# ramtotsop.net
KiCad netlist of a schematic drawn in EAGLE
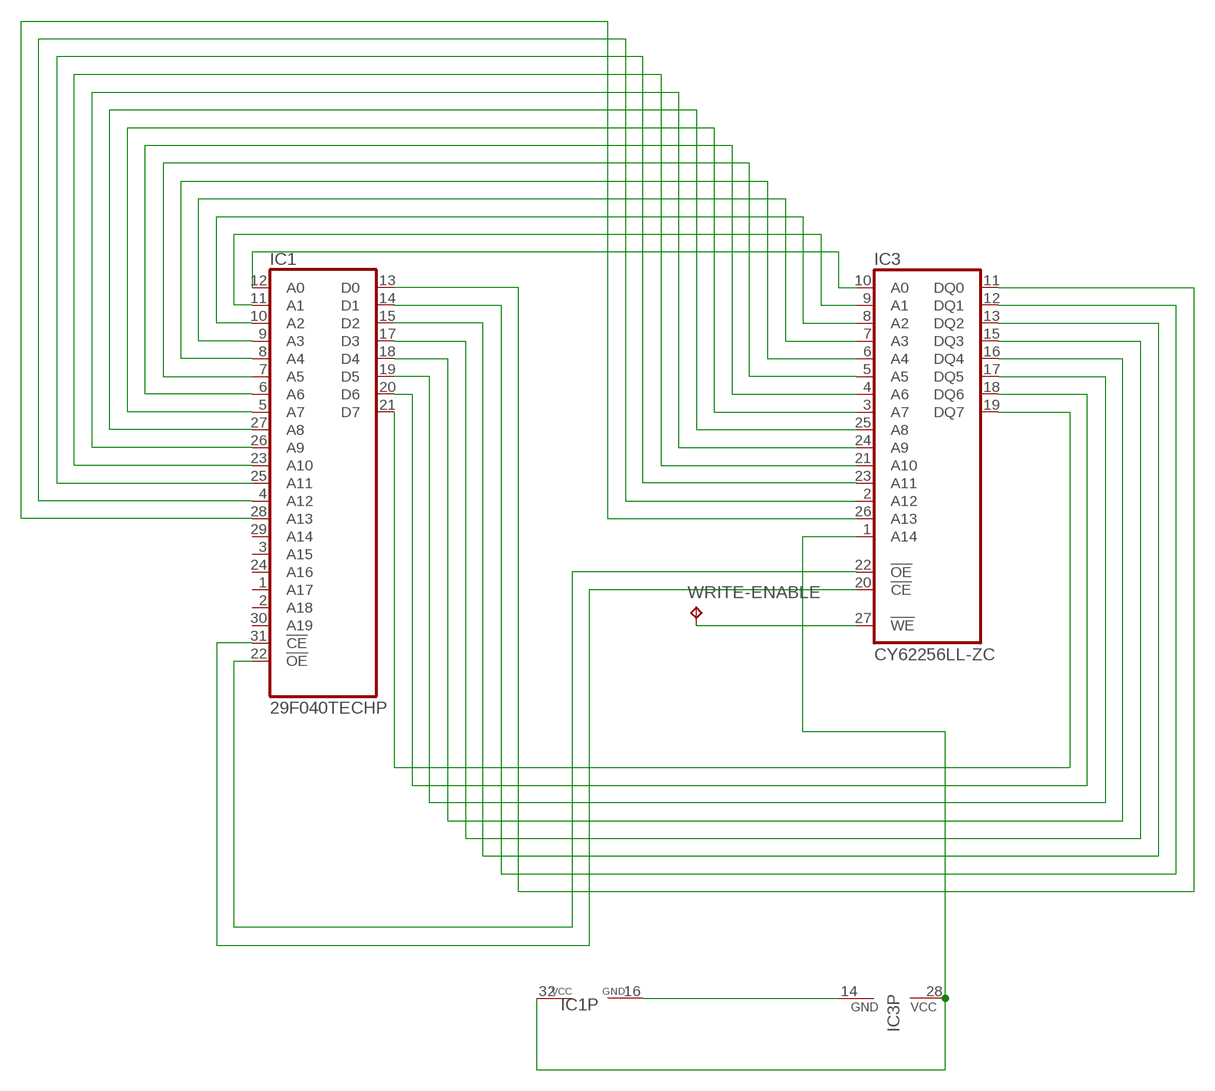
[diagram p0: schematic, sheet 1]

(export (version "E")
  (design (tool "Eeschema 10.0.6"))
  (components
    (comp (ref "IC1")
      (value "29F040TECHP")
      (footprint "eagle-import:DIL32-3")
      (libsource (lib "eagle-import") (part "29F040PTECH"))
    )
    (comp (ref "IC3")
      (value "CY62256LL-ZC")
      (footprint "eagle-import:TSOP1-28")
      (libsource (lib "eagle-import") (part "CY62256LL-?ZC"))
    )
    (comp (ref "WRITE-ENABLE")
      (value "TPTP20SQ")
      (footprint "eagle-import:TP20SQ")
      (libsource (lib "eagle-import") (part "TPTP20SQ"))
    )
  )
  (nets
    (net (code "1") (name "Net-(IC1A-A0)") (class "Default")
      (node (ref "IC1") (pin "12") (pinfunction "A0_12") (pintype "input"))
      (node (ref "IC3") (pin "10") (pinfunction "A0_10") (pintype "input"))
    )
    (net (code "2") (name "Net-(IC1A-A1)") (class "Default")
      (node (ref "IC1") (pin "11") (pinfunction "A1_11") (pintype "input"))
      (node (ref "IC3") (pin "9") (pinfunction "A1_9") (pintype "input"))
    )
    (net (code "3") (name "Net-(IC1A-A2)") (class "Default")
      (node (ref "IC1") (pin "10") (pinfunction "A2_10") (pintype "input"))
      (node (ref "IC3") (pin "8") (pinfunction "A2_8") (pintype "input"))
    )
    (net (code "4") (name "Net-(IC1A-A3)") (class "Default")
      (node (ref "IC1") (pin "9") (pinfunction "A3_9") (pintype "input"))
      (node (ref "IC3") (pin "7") (pinfunction "A3_7") (pintype "input"))
    )
    (net (code "5") (name "Net-(IC1A-A4)") (class "Default")
      (node (ref "IC1") (pin "8") (pinfunction "A4_8") (pintype "input"))
      (node (ref "IC3") (pin "6") (pinfunction "A4_6") (pintype "input"))
    )
    (net (code "6") (name "Net-(IC1A-A5)") (class "Default")
      (node (ref "IC1") (pin "7") (pinfunction "A5_7") (pintype "input"))
      (node (ref "IC3") (pin "5") (pinfunction "A5_5") (pintype "input"))
    )
    (net (code "7") (name "Net-(IC1A-A6)") (class "Default")
      (node (ref "IC1") (pin "6") (pinfunction "A6_6") (pintype "input"))
      (node (ref "IC3") (pin "4") (pinfunction "A6_4") (pintype "input"))
    )
    (net (code "8") (name "Net-(IC1A-A7)") (class "Default")
      (node (ref "IC1") (pin "5") (pinfunction "A7_5") (pintype "input"))
      (node (ref "IC3") (pin "3") (pinfunction "A7_3") (pintype "input"))
    )
    (net (code "9") (name "Net-(IC1A-A8)") (class "Default")
      (node (ref "IC1") (pin "27") (pinfunction "A8_27") (pintype "input"))
      (node (ref "IC3") (pin "25") (pinfunction "A8_25") (pintype "input"))
    )
    (net (code "10") (name "Net-(IC1A-A9)") (class "Default")
      (node (ref "IC1") (pin "26") (pinfunction "A9_26") (pintype "input"))
      (node (ref "IC3") (pin "24") (pinfunction "A9_24") (pintype "input"))
    )
    (net (code "11") (name "Net-(IC1A-A10)") (class "Default")
      (node (ref "IC1") (pin "23") (pinfunction "A10_23") (pintype "input"))
      (node (ref "IC3") (pin "21") (pinfunction "A10_21") (pintype "input"))
    )
    (net (code "12") (name "Net-(IC1A-A11)") (class "Default")
      (node (ref "IC1") (pin "25") (pinfunction "A11_25") (pintype "input"))
      (node (ref "IC3") (pin "23") (pinfunction "A11_23") (pintype "input"))
    )
    (net (code "13") (name "Net-(IC1A-A12)") (class "Default")
      (node (ref "IC1") (pin "4") (pinfunction "A12_4") (pintype "input"))
      (node (ref "IC3") (pin "2") (pinfunction "A12_2") (pintype "input"))
    )
    (net (code "14") (name "Net-(IC1A-A13)") (class "Default")
      (node (ref "IC1") (pin "28") (pinfunction "A13_28") (pintype "input"))
      (node (ref "IC3") (pin "26") (pinfunction "A13_26") (pintype "input"))
    )
    (net (code "15") (name "Net-(IC1A-D0)") (class "Default")
      (node (ref "IC1") (pin "13") (pinfunction "D0_13") (pintype "tri_state"))
      (node (ref "IC3") (pin "11") (pinfunction "DQ0_11") (pintype "bidirectional"))
    )
    (net (code "16") (name "Net-(IC1A-D1)") (class "Default")
      (node (ref "IC1") (pin "14") (pinfunction "D1_14") (pintype "tri_state"))
      (node (ref "IC3") (pin "12") (pinfunction "DQ1_12") (pintype "bidirectional"))
    )
    (net (code "17") (name "Net-(IC1A-D2)") (class "Default")
      (node (ref "IC1") (pin "15") (pinfunction "D2_15") (pintype "tri_state"))
      (node (ref "IC3") (pin "13") (pinfunction "DQ2_13") (pintype "bidirectional"))
    )
    (net (code "18") (name "Net-(IC1A-D3)") (class "Default")
      (node (ref "IC1") (pin "17") (pinfunction "D3_17") (pintype "tri_state"))
      (node (ref "IC3") (pin "15") (pinfunction "DQ3_15") (pintype "bidirectional"))
    )
    (net (code "19") (name "Net-(IC1A-D4)") (class "Default")
      (node (ref "IC1") (pin "18") (pinfunction "D4_18") (pintype "tri_state"))
      (node (ref "IC3") (pin "16") (pinfunction "DQ4_16") (pintype "bidirectional"))
    )
    (net (code "20") (name "Net-(IC1A-D5)") (class "Default")
      (node (ref "IC1") (pin "19") (pinfunction "D5_19") (pintype "tri_state"))
      (node (ref "IC3") (pin "17") (pinfunction "DQ5_17") (pintype "bidirectional"))
    )
    (net (code "21") (name "Net-(IC1A-D6)") (class "Default")
      (node (ref "IC1") (pin "20") (pinfunction "D6_20") (pintype "tri_state"))
      (node (ref "IC3") (pin "18") (pinfunction "DQ6_18") (pintype "bidirectional"))
    )
    (net (code "22") (name "Net-(IC1A-D7)") (class "Default")
      (node (ref "IC1") (pin "21") (pinfunction "D7_21") (pintype "input"))
      (node (ref "IC3") (pin "19") (pinfunction "DQ7_19") (pintype "bidirectional"))
    )
    (net (code "23") (name "Net-(IC1A-~{CE})") (class "Default")
      (node (ref "IC1") (pin "31") (pinfunction "~{CE}_31") (pintype "input"))
      (node (ref "IC3") (pin "20") (pinfunction "~{CE}_20") (pintype "input"))
    )
    (net (code "24") (name "Net-(IC1A-~{OE})") (class "Default")
      (node (ref "IC1") (pin "22") (pinfunction "~{OE}_22") (pintype "input"))
      (node (ref "IC3") (pin "22") (pinfunction "~{OE}_22") (pintype "input"))
    )
    (net (code "25") (name "Net-(IC1B-GND)") (class "Default")
      (node (ref "IC1") (pin "16") (pinfunction "GND_16") (pintype "power_in"))
      (node (ref "IC3") (pin "14") (pinfunction "GND_14") (pintype "power_in"))
    )
    (net (code "26") (name "Net-(IC1B-VCC)") (class "Default")
      (node (ref "IC1") (pin "32") (pinfunction "VCC_32") (pintype "power_in"))
      (node (ref "IC3") (pin "1") (pinfunction "A14_1") (pintype "input"))
      (node (ref "IC3") (pin "28") (pinfunction "VCC_28") (pintype "power_in"))
    )
    (net (code "27") (name "Net-(IC3A-~{WE})") (class "Default")
      (node (ref "IC3") (pin "27") (pinfunction "~{WE}_27") (pintype "input"))
      (node (ref "WRITE-ENABLE") (pin "TP") (pinfunction "TP_TP") (pintype "input"))
    )
    (net (code "28") (name "unconnected-(IC1A-A14-Pad29)") (class "Default")
      (node (ref "IC1") (pin "29") (pinfunction "A14_29") (pintype "input"))
    )
    (net (code "29") (name "unconnected-(IC1A-A15-Pad3)") (class "Default")
      (node (ref "IC1") (pin "3") (pinfunction "A15_3") (pintype "input"))
    )
    (net (code "30") (name "unconnected-(IC1A-A16-Pad24)") (class "Default")
      (node (ref "IC1") (pin "24") (pinfunction "A16_24") (pintype "input"))
    )
    (net (code "31") (name "unconnected-(IC1A-A17-Pad1)") (class "Default")
      (node (ref "IC1") (pin "1") (pinfunction "A17_1") (pintype "input"))
    )
    (net (code "32") (name "unconnected-(IC1A-A18-Pad2)") (class "Default")
      (node (ref "IC1") (pin "2") (pinfunction "A18_2") (pintype "input"))
    )
    (net (code "33") (name "unconnected-(IC1A-A19-Pad30)") (class "Default")
      (node (ref "IC1") (pin "30") (pinfunction "A19_30") (pintype "input"))
    )
  )
)
